# ai_breakout_microusb.net
KiCad netlist of a schematic drawn in EAGLE
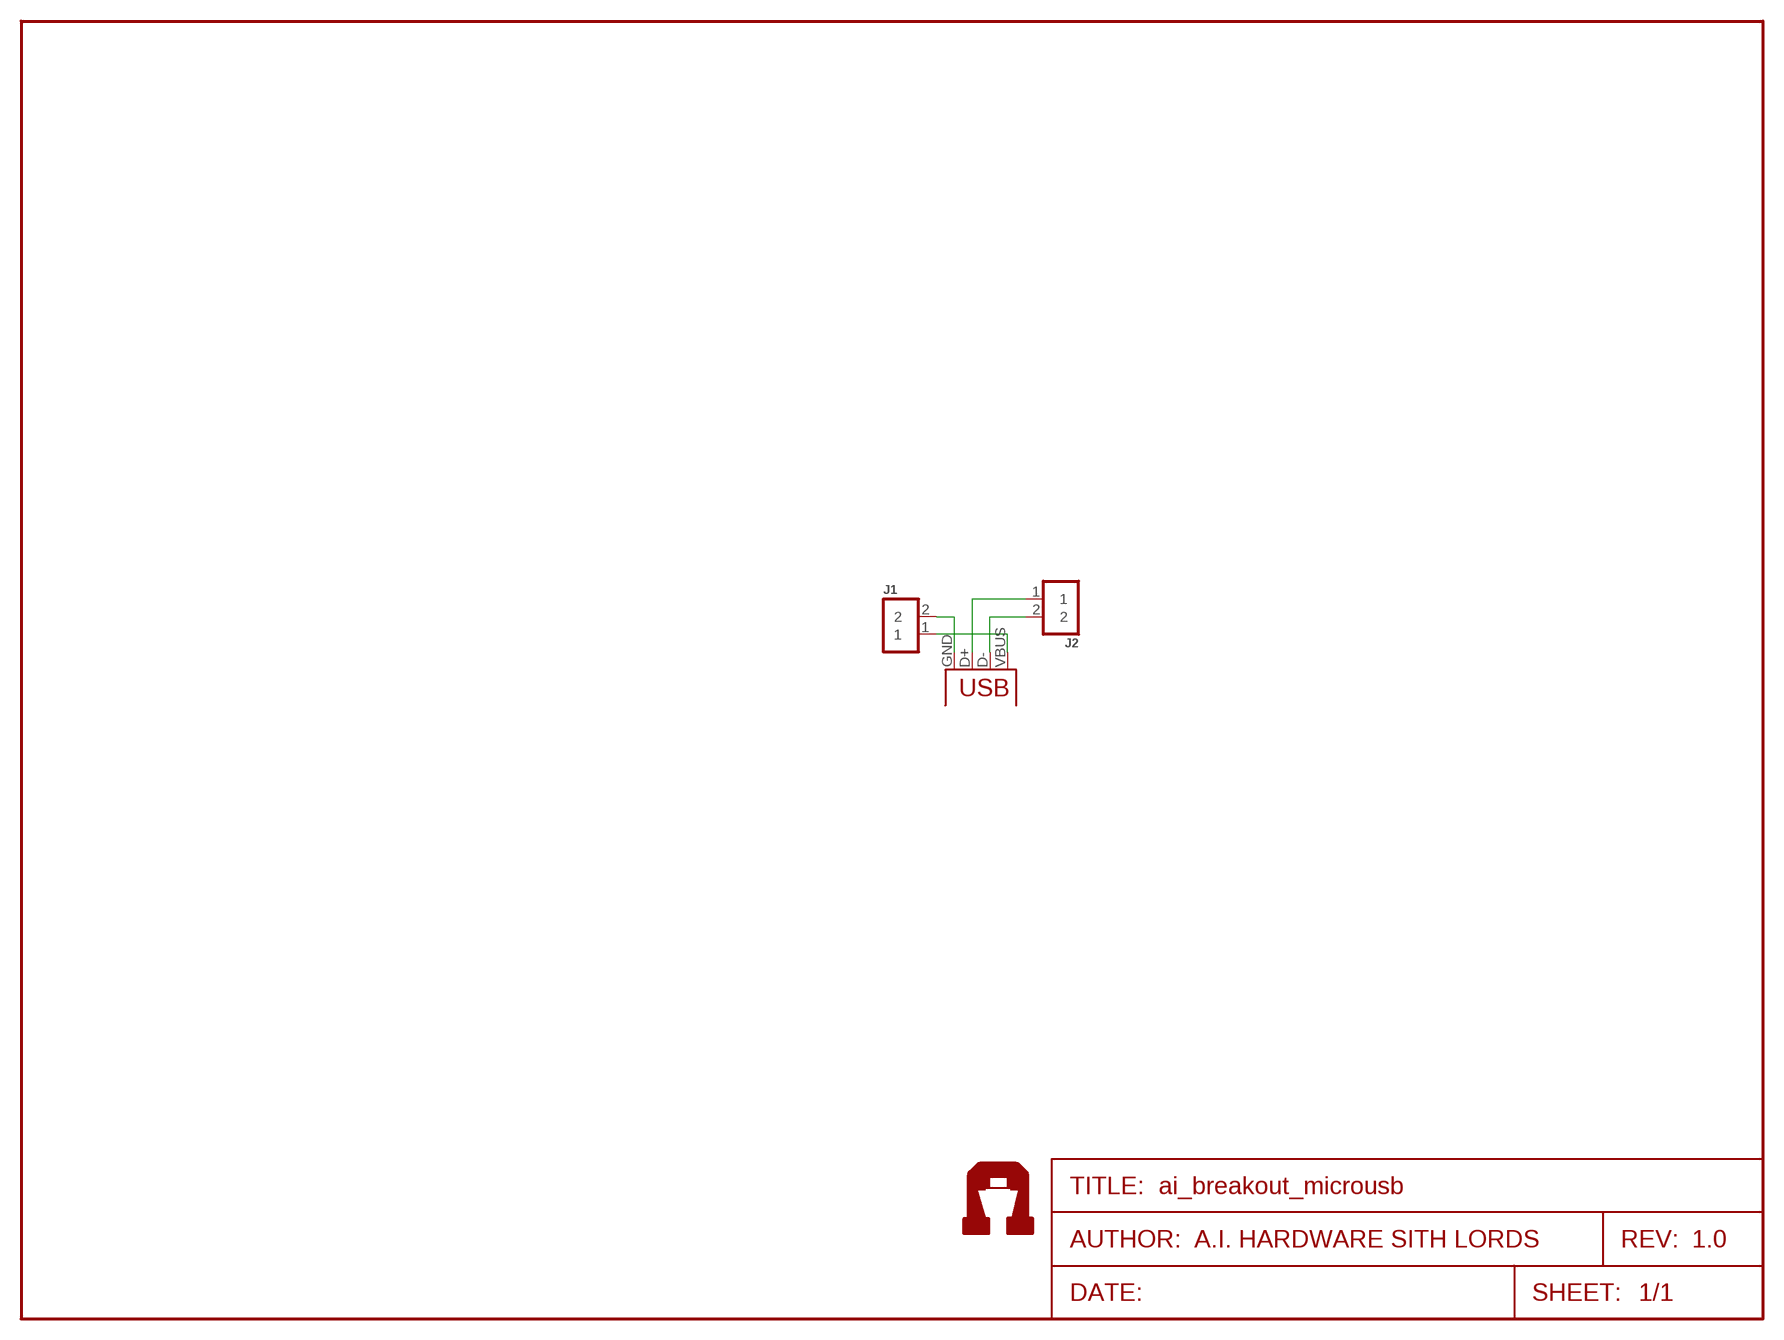
[diagram p0: schematic, sheet 1]

(export (version "E")
  (design (tool "Eeschema 10.0.6"))
  (components
    (comp (ref "J1")
      (value "1X02")
      (footprint "eagle-import:1X02")
      (libsource (lib "eagle-import") (part "1X02"))
    )
    (comp (ref "J2")
      (value "1X02NOFIRST")
      (footprint "eagle-import:1X02-NOFIRST")
      (libsource (lib "eagle-import") (part "1X02NOFIRST"))
    )
    (comp (ref "U$2")
      (value "AI-LOGOXS")
      (footprint "eagle-import:AI-LOGO-XS")
      (libsource (lib "eagle-import") (part "AI-LOGOXS"))
    )
    (comp (ref "USB1")
      (value "USBMICROB-TH")
      (footprint "eagle-import:USB-MICROB-TH")
      (libsource (lib "eagle-import") (part "USBMICROB-TH"))
    )
  )
  (nets
    (net (code "1") (name "Net-(J1-Pad1)") (class "Default")
      (node (ref "J1") (pin "1") (pinfunction "1_1") (pintype "bidirectional"))
      (node (ref "USB1") (pin "VBUS") (pinfunction "VBUS_VBUS") (pintype "bidirectional"))
    )
    (net (code "2") (name "Net-(J1-Pad2)") (class "Default")
      (node (ref "J1") (pin "2") (pinfunction "2_2") (pintype "bidirectional"))
      (node (ref "USB1") (pin "GND") (pinfunction "GND_GND") (pintype "bidirectional"))
    )
    (net (code "3") (name "Net-(J2-Pad1)") (class "Default")
      (node (ref "J2") (pin "1") (pinfunction "1_1") (pintype "bidirectional"))
      (node (ref "USB1") (pin "D+") (pinfunction "D+_D+") (pintype "bidirectional"))
    )
    (net (code "4") (name "Net-(J2-Pad2)") (class "Default")
      (node (ref "J2") (pin "2") (pinfunction "2_2") (pintype "bidirectional"))
      (node (ref "USB1") (pin "D-") (pinfunction "D-_D-") (pintype "bidirectional"))
    )
  )
)
